# encoder_cable_breakout.net
KiCad netlist of a schematic drawn in EAGLE
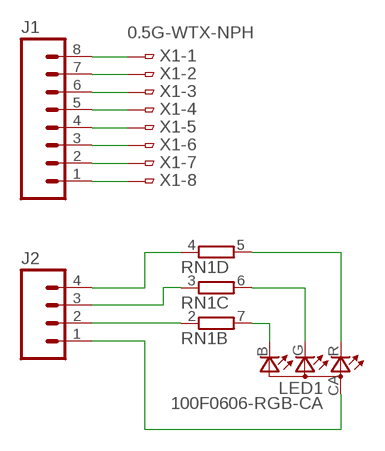
[diagram p0: schematic, sheet 1]

(export (version "E")
  (design (tool "Eeschema 10.0.6"))
  (components
    (comp (ref "J1")
      (value "M08SILK_FEMALE_PTH")
      (footprint "eagle-import:1X08")
      (libsource (lib "eagle-import") (part "M08SILK_FEMALE_PTH"))
    )
    (comp (ref "J2")
      (value "M04PTH")
      (footprint "eagle-import:1X04")
      (libsource (lib "eagle-import") (part "M04PTH"))
    )
    (comp (ref "LED1")
      (value "100F0606-RGB-CA")
      (footprint "eagle-import:1616")
      (libsource (lib "eagle-import") (part "100F0606-RGB-CA"))
    )
    (comp (ref "RN1")
      (value "4R-NYC124")
      (footprint "eagle-import:YC124")
      (libsource (lib "eagle-import") (part "4R-NYC124"))
    )
    (comp (ref "X1")
      (value "0.5G-WTX-NPH")
      (footprint "eagle-import:0.5G-WTX-NP")
      (fields (field (name "MPN") "0.5G-WTX-nP"))
      (libsource (lib "eagle-import") (part "0.5G-WTX-NPH"))
    )
  )
  (nets
    (net (code "1") (name "Net-(J1-Pad8)") (class "Default")
      (node (ref "J1") (pin "8") (pinfunction "8_8") (pintype "passive"))
      (node (ref "X1") (pin "1") (pinfunction "1_1") (pintype "passive"))
    )
    (net (code "2") (name "Net-(J2-Pad1)") (class "Default")
      (node (ref "J2") (pin "1") (pinfunction "1_1") (pintype "passive"))
      (node (ref "LED1") (pin "CA") (pinfunction "CA_CA") (pintype "passive"))
    )
    (net (code "3") (name "Net-(RN1B-1)") (class "Default")
      (node (ref "J2") (pin "2") (pinfunction "2_2") (pintype "passive"))
      (node (ref "RN1") (pin "2") (pinfunction "1_2") (pintype "passive"))
    )
    (net (code "4") (name "Net-(RN1B-2)") (class "Default")
      (node (ref "LED1") (pin "B") (pinfunction "B_B") (pintype "passive"))
      (node (ref "RN1") (pin "7") (pinfunction "2_7") (pintype "passive"))
    )
    (net (code "5") (name "Net-(RN1C-1)") (class "Default")
      (node (ref "J2") (pin "3") (pinfunction "3_3") (pintype "passive"))
      (node (ref "RN1") (pin "3") (pinfunction "1_3") (pintype "passive"))
    )
    (net (code "6") (name "Net-(RN1C-2)") (class "Default")
      (node (ref "LED1") (pin "G") (pinfunction "G_G") (pintype "passive"))
      (node (ref "RN1") (pin "6") (pinfunction "2_6") (pintype "passive"))
    )
    (net (code "7") (name "Net-(RN1D-1)") (class "Default")
      (node (ref "J2") (pin "4") (pinfunction "4_4") (pintype "passive"))
      (node (ref "RN1") (pin "4") (pinfunction "1_4") (pintype "passive"))
    )
    (net (code "8") (name "Net-(RN1D-2)") (class "Default")
      (node (ref "LED1") (pin "R") (pinfunction "R_R") (pintype "passive"))
      (node (ref "RN1") (pin "5") (pinfunction "2_5") (pintype "passive"))
    )
    (net (code "9") (name "Net-(X1B-1)") (class "Default")
      (node (ref "J1") (pin "7") (pinfunction "7_7") (pintype "passive"))
      (node (ref "X1") (pin "2") (pinfunction "1_2") (pintype "passive"))
    )
    (net (code "10") (name "Net-(X1C-1)") (class "Default")
      (node (ref "J1") (pin "6") (pinfunction "6_6") (pintype "passive"))
      (node (ref "X1") (pin "3") (pinfunction "1_3") (pintype "passive"))
    )
    (net (code "11") (name "Net-(X1D-1)") (class "Default")
      (node (ref "J1") (pin "5") (pinfunction "5_5") (pintype "passive"))
      (node (ref "X1") (pin "4") (pinfunction "1_4") (pintype "passive"))
    )
    (net (code "12") (name "Net-(X1E-1)") (class "Default")
      (node (ref "J1") (pin "4") (pinfunction "4_4") (pintype "passive"))
      (node (ref "X1") (pin "5") (pinfunction "1_5") (pintype "passive"))
    )
    (net (code "13") (name "Net-(X1F-1)") (class "Default")
      (node (ref "J1") (pin "3") (pinfunction "3_3") (pintype "passive"))
      (node (ref "X1") (pin "6") (pinfunction "1_6") (pintype "passive"))
    )
    (net (code "14") (name "Net-(X1G-1)") (class "Default")
      (node (ref "J1") (pin "2") (pinfunction "2_2") (pintype "passive"))
      (node (ref "X1") (pin "7") (pinfunction "1_7") (pintype "passive"))
    )
    (net (code "15") (name "Net-(X1H-1)") (class "Default")
      (node (ref "J1") (pin "1") (pinfunction "1_1") (pintype "passive"))
      (node (ref "X1") (pin "8") (pinfunction "1_8") (pintype "passive"))
    )
  )
)
